# A-Headers.net
KiCad netlist of a schematic drawn in Altium Designer
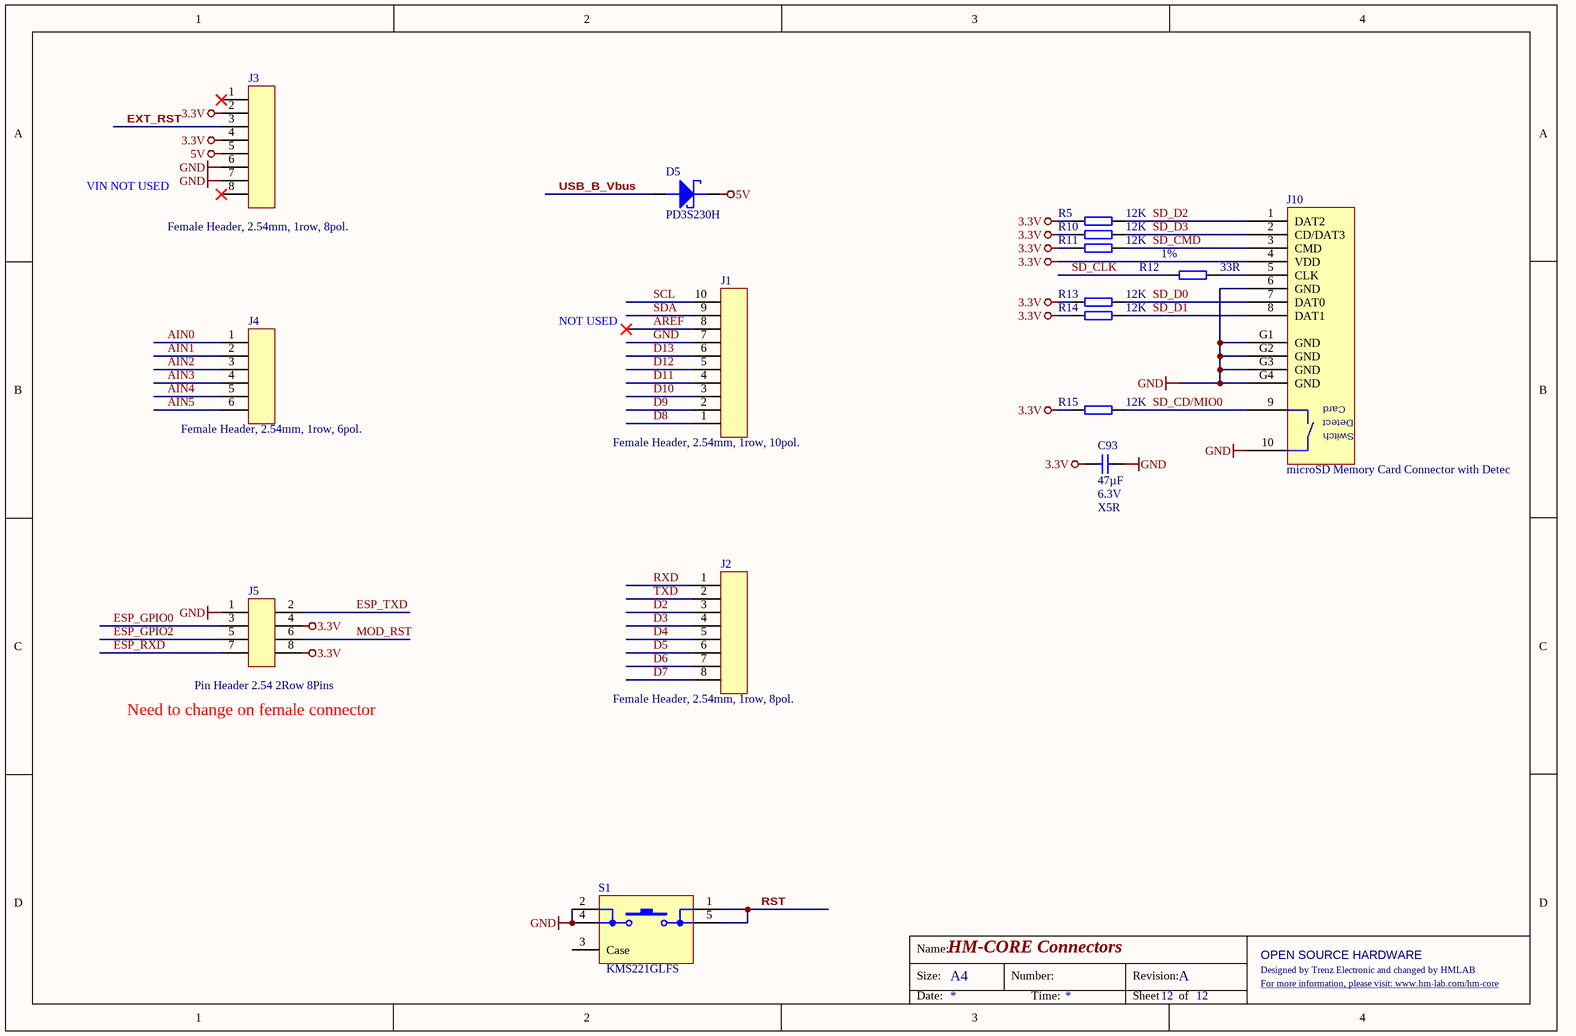
[diagram p0: A-Headers.SchDoc]

(export (version "E")
  (design (tool "Eeschema 10.0.6"))
  (components
    (comp (ref "C93")
      (value "47µF")
      (footprint "CAPC2012X135N")
      (description "KON 47µF 6,3V  X5R SMD 20%")
      (fields
        (field (name "VOLTAGE") "6.3V")
        (field (name "TECHNOLOGY") "X5R")
        (field (name "TOLERANCE") "20%")
      )
      (libsource (lib "TE") (part "CAP-NP"))
    )
    (comp (ref "D5") (value "PD3S230H") (footprint "PowerDI323") (libsource (lib "TE") (part "SCHOTTKY")))
    (comp (ref "J1")
      (value "Female Header, 2.54mm, 1row, 10pol.")
      (footprint "BUCHSENLEISTE-2.54-10-1R")
      (description "Buchsenleiste 1 reihig präz. 10 pol.")
      (libsource (lib "TE") (part "CON-10"))
    )
    (comp (ref "J2")
      (value "Female Header, 2.54mm, 1row, 8pol.")
      (footprint "BUCHSENLEISTE-2.54-8-1R")
      (description "Buchsenleiste 1 reihig präz. 8 pol.")
      (libsource (lib "") (part "CON-8_1"))
    )
    (comp (ref "J3")
      (value "Female Header, 2.54mm, 1row, 8pol.")
      (footprint "BUCHSENLEISTE-2.54-8-1R")
      (description "Buchsenleiste 1 reihig präz. 8 pol.")
      (libsource (lib "") (part "CON-8_1"))
    )
    (comp (ref "J4")
      (value "Female Header, 2.54mm, 1row, 6pol.")
      (footprint "BUCHSENLEISTE-2.54-6-1R")
      (description "Buchsenleiste 1 reihig präz. 6 pol.")
      (libsource (lib "TE") (part "CON-6"))
    )
    (comp (ref "J5")
      (value "Pin Header 2.54 2Row 8Pins")
      (footprint "STIFTLEISTE2_54 OG 2R-8")
      (description "Stiftleiste gerade 2-reihig, 8pol.")
      (libsource (lib "TE") (part "CON-8"))
    )
    (comp (ref "J10")
      (value "microSD Memory Card Connector with Detec")
      (footprint "104031-0811")
      (description "microSD Memory Card Connector with Detect Switch")
      (libsource (lib "TE") (part "104031-0811"))
    )
    (comp (ref "R5")
      (value "12K")
      (footprint "RESC1005X40N")
      (description "WID SMD 12K 1% 0,063W")
      (libsource (lib "TE") (part "RES"))
    )
    (comp (ref "R10")
      (value "12K")
      (footprint "RESC1005X40N")
      (description "WID SMD 12K 1% 0,063W")
      (libsource (lib "TE") (part "RES"))
    )
    (comp (ref "R11")
      (value "12K")
      (footprint "RESC1005X40N")
      (description "WID SMD 12K 1% 0,063W")
      (libsource (lib "TE") (part "RES"))
    )
    (comp (ref "R12")
      (value "33R")
      (footprint "RESC0603X26N")
      (description "WID SMD 33R 1% 0,05W")
      (fields (field (name "TOLERANCE") "1%"))
      (libsource (lib "TE") (part "RES"))
    )
    (comp (ref "R13")
      (value "12K")
      (footprint "RESC1005X40N")
      (description "WID SMD 12K 1% 0,063W")
      (libsource (lib "TE") (part "RES"))
    )
    (comp (ref "R14")
      (value "12K")
      (footprint "RESC1005X40N")
      (description "WID SMD 12K 1% 0,063W")
      (libsource (lib "TE") (part "RES"))
    )
    (comp (ref "R15")
      (value "12K")
      (footprint "RESC1005X40N")
      (description "WID SMD 12K 1% 0,063W")
      (libsource (lib "TE") (part "RES"))
    )
    (comp (ref "S1")
      (value "KMS221GLFS")
      (footprint "KMS2xxGLFS")
      (description "KMS221GLFS - SWITCH, SPST, 0.05A, 32VDC, SMD")
      (libsource (lib "TE") (part "KMS2xxGLFS"))
    )
  )
  (nets
    (net (code "1") (name "/AIN0") (class "Default") (node (ref "J4") (pin "1") (pintype "passive")))
    (net (code "2") (name "/AIN1") (class "Default") (node (ref "J4") (pin "2") (pintype "passive")))
    (net (code "3") (name "/AIN2") (class "Default") (node (ref "J4") (pin "3") (pintype "passive")))
    (net (code "4") (name "/AIN3") (class "Default") (node (ref "J4") (pin "4") (pintype "passive")))
    (net (code "5") (name "/AIN4") (class "Default") (node (ref "J4") (pin "5") (pintype "passive")))
    (net (code "6") (name "/AIN5") (class "Default") (node (ref "J4") (pin "6") (pintype "passive")))
    (net (code "7") (name "/AREF") (class "Default")
      (node (ref "J1") (pin "8") (pinfunction "8_8") (pintype "passive+no_connect"))
    )
    (net (code "8") (name "/D2") (class "Default") (node (ref "J2") (pin "3") (pintype "passive")))
    (net (code "9") (name "/D3") (class "Default") (node (ref "J2") (pin "4") (pintype "passive")))
    (net (code "10") (name "/D4") (class "Default") (node (ref "J2") (pin "5") (pintype "passive")))
    (net (code "11") (name "/D5") (class "Default") (node (ref "J2") (pin "6") (pintype "passive")))
    (net (code "12") (name "/D6") (class "Default") (node (ref "J2") (pin "7") (pintype "passive")))
    (net (code "13") (name "/D7") (class "Default") (node (ref "J2") (pin "8") (pintype "passive")))
    (net (code "14") (name "/D8") (class "Default")
      (node (ref "J1") (pin "1") (pinfunction "1_1") (pintype "passive"))
    )
    (net (code "15") (name "/D9") (class "Default")
      (node (ref "J1") (pin "2") (pinfunction "2_2") (pintype "passive"))
    )
    (net (code "16") (name "/D10") (class "Default")
      (node (ref "J1") (pin "3") (pinfunction "3_3") (pintype "passive"))
    )
    (net (code "17") (name "/D11") (class "Default")
      (node (ref "J1") (pin "4") (pinfunction "4_4") (pintype "passive"))
    )
    (net (code "18") (name "/D12") (class "Default")
      (node (ref "J1") (pin "5") (pinfunction "5_5") (pintype "passive"))
    )
    (net (code "19") (name "/D13") (class "Default")
      (node (ref "J1") (pin "6") (pinfunction "6_6") (pintype "passive"))
    )
    (net (code "20") (name "/ESP_GPIO0") (class "Default") (node (ref "J5") (pin "3") (pintype "passive")))
    (net (code "21") (name "/ESP_GPIO2") (class "Default") (node (ref "J5") (pin "5") (pintype "passive")))
    (net (code "22") (name "/ESP_RXD") (class "Default") (node (ref "J5") (pin "7") (pintype "passive")))
    (net (code "23") (name "/ESP_TXD") (class "Default") (node (ref "J5") (pin "2") (pintype "passive")))
    (net (code "24") (name "/EXT_RST") (class "Default") (node (ref "J3") (pin "3") (pintype "passive")))
    (net (code "25") (name "/MOD_RST") (class "Default") (node (ref "J5") (pin "6") (pintype "passive")))
    (net (code "26") (name "/RST") (class "Default")
      (node (ref "S1") (pin "1") (pinfunction "1_1") (pintype "passive"))
      (node (ref "S1") (pin "5") (pinfunction "5_5") (pintype "passive"))
    )
    (net (code "27") (name "/RXD") (class "Default") (node (ref "J2") (pin "1") (pintype "passive")))
    (net (code "28") (name "/SCL") (class "Default")
      (node (ref "J1") (pin "10") (pinfunction "10_10") (pintype "passive"))
    )
    (net (code "29") (name "/SDA") (class "Default")
      (node (ref "J1") (pin "9") (pinfunction "9_9") (pintype "passive"))
    )
    (net (code "30") (name "/SD_CD{slash}MIO0") (class "Default")
      (node (ref "J10") (pin "9") (pinfunction "CDSW_9") (pintype "passive"))
      (node (ref "R15") (pin "2") (pinfunction "2_2") (pintype "passive"))
    )
    (net (code "31") (name "/SD_CLK") (class "Default")
      (node (ref "R12") (pin "1") (pinfunction "1_1") (pintype "passive"))
    )
    (net (code "32") (name "/SD_CMD") (class "Default")
      (node (ref "J10") (pin "3") (pinfunction "CMD_3") (pintype "passive"))
      (node (ref "R11") (pin "2") (pinfunction "2_2") (pintype "passive"))
    )
    (net (code "33") (name "/SD_D0") (class "Default")
      (node (ref "J10") (pin "7") (pinfunction "DAT0_7") (pintype "passive"))
      (node (ref "R13") (pin "2") (pinfunction "2_2") (pintype "passive"))
    )
    (net (code "34") (name "/SD_D1") (class "Default")
      (node (ref "J10") (pin "8") (pinfunction "DAT1_8") (pintype "passive"))
      (node (ref "R14") (pin "2") (pinfunction "2_2") (pintype "passive"))
    )
    (net (code "35") (name "/SD_D2") (class "Default")
      (node (ref "J10") (pin "1") (pinfunction "DAT2_1") (pintype "passive"))
      (node (ref "R5") (pin "2") (pinfunction "2_2") (pintype "passive"))
    )
    (net (code "36") (name "/SD_D3") (class "Default")
      (node (ref "J10") (pin "2") (pinfunction "CD/DAT3_2") (pintype "passive"))
      (node (ref "R10") (pin "2") (pinfunction "2_2") (pintype "passive"))
    )
    (net (code "37") (name "/TXD") (class "Default") (node (ref "J2") (pin "2") (pintype "passive")))
    (net (code "38") (name "/USB_B_Vbus") (class "Default")
      (node (ref "D5") (pin "2") (pinfunction "ANODE_2") (pintype "passive"))
    )
    (net (code "39") (name "3.3V") (class "Default")
      (node (ref "C93") (pin "1") (pinfunction "1_1") (pintype "passive"))
      (node (ref "J10") (pin "4") (pinfunction "VDD_4") (pintype "passive"))
      (node (ref "J3") (pin "2") (pintype "passive"))
      (node (ref "J3") (pin "4") (pintype "passive"))
      (node (ref "J5") (pin "4") (pintype "passive"))
      (node (ref "J5") (pin "8") (pintype "passive"))
      (node (ref "R10") (pin "1") (pinfunction "1_1") (pintype "passive"))
      (node (ref "R11") (pin "1") (pinfunction "1_1") (pintype "passive"))
      (node (ref "R13") (pin "1") (pinfunction "1_1") (pintype "passive"))
      (node (ref "R14") (pin "1") (pinfunction "1_1") (pintype "passive"))
      (node (ref "R15") (pin "1") (pinfunction "1_1") (pintype "passive"))
      (node (ref "R5") (pin "1") (pinfunction "1_1") (pintype "passive"))
    )
    (net (code "40") (name "5V") (class "Default")
      (node (ref "D5") (pin "1") (pinfunction "KATHODE_1") (pintype "passive"))
      (node (ref "J3") (pin "5") (pintype "passive"))
    )
    (net (code "41") (name "GND") (class "Default")
      (node (ref "C93") (pin "2") (pinfunction "2_2") (pintype "passive"))
      (node (ref "J1") (pin "7") (pinfunction "7_7") (pintype "passive"))
      (node (ref "J10") (pin "10") (pinfunction "CDSW_10") (pintype "passive"))
      (node (ref "J10") (pin "6") (pinfunction "GND_6") (pintype "passive"))
      (node (ref "J10") (pin "G1") (pinfunction "GND_G1") (pintype "passive"))
      (node (ref "J10") (pin "G2") (pinfunction "GND_G2") (pintype "passive"))
      (node (ref "J10") (pin "G3") (pinfunction "GND_G3") (pintype "passive"))
      (node (ref "J10") (pin "G4") (pinfunction "GND_G4") (pintype "passive"))
      (node (ref "J3") (pin "6") (pintype "passive"))
      (node (ref "J3") (pin "7") (pintype "passive"))
      (node (ref "J5") (pin "1") (pintype "passive"))
      (node (ref "S1") (pin "2") (pinfunction "2_2") (pintype "passive"))
      (node (ref "S1") (pin "4") (pinfunction "4_4") (pintype "passive"))
    )
    (net (code "42") (name "Net-(J10-CLK)") (class "Default")
      (node (ref "J10") (pin "5") (pinfunction "CLK_5") (pintype "passive"))
      (node (ref "R12") (pin "2") (pinfunction "2_2") (pintype "passive"))
    )
    (net (code "43") (name "unconnected-(J3-Pad1)") (class "Default")
      (node (ref "J3") (pin "1") (pintype "passive+no_connect"))
    )
    (net (code "44") (name "unconnected-(J3-Pad8)") (class "Default")
      (node (ref "J3") (pin "8") (pintype "passive+no_connect"))
    )
    (net (code "45") (name "unconnected-(S1-Case-Pad3)") (class "Default")
      (node (ref "S1") (pin "3") (pinfunction "Case_3") (pintype "passive"))
    )
  )
)
